# Esquematico.net
KiCad netlist of a schematic drawn in EAGLE
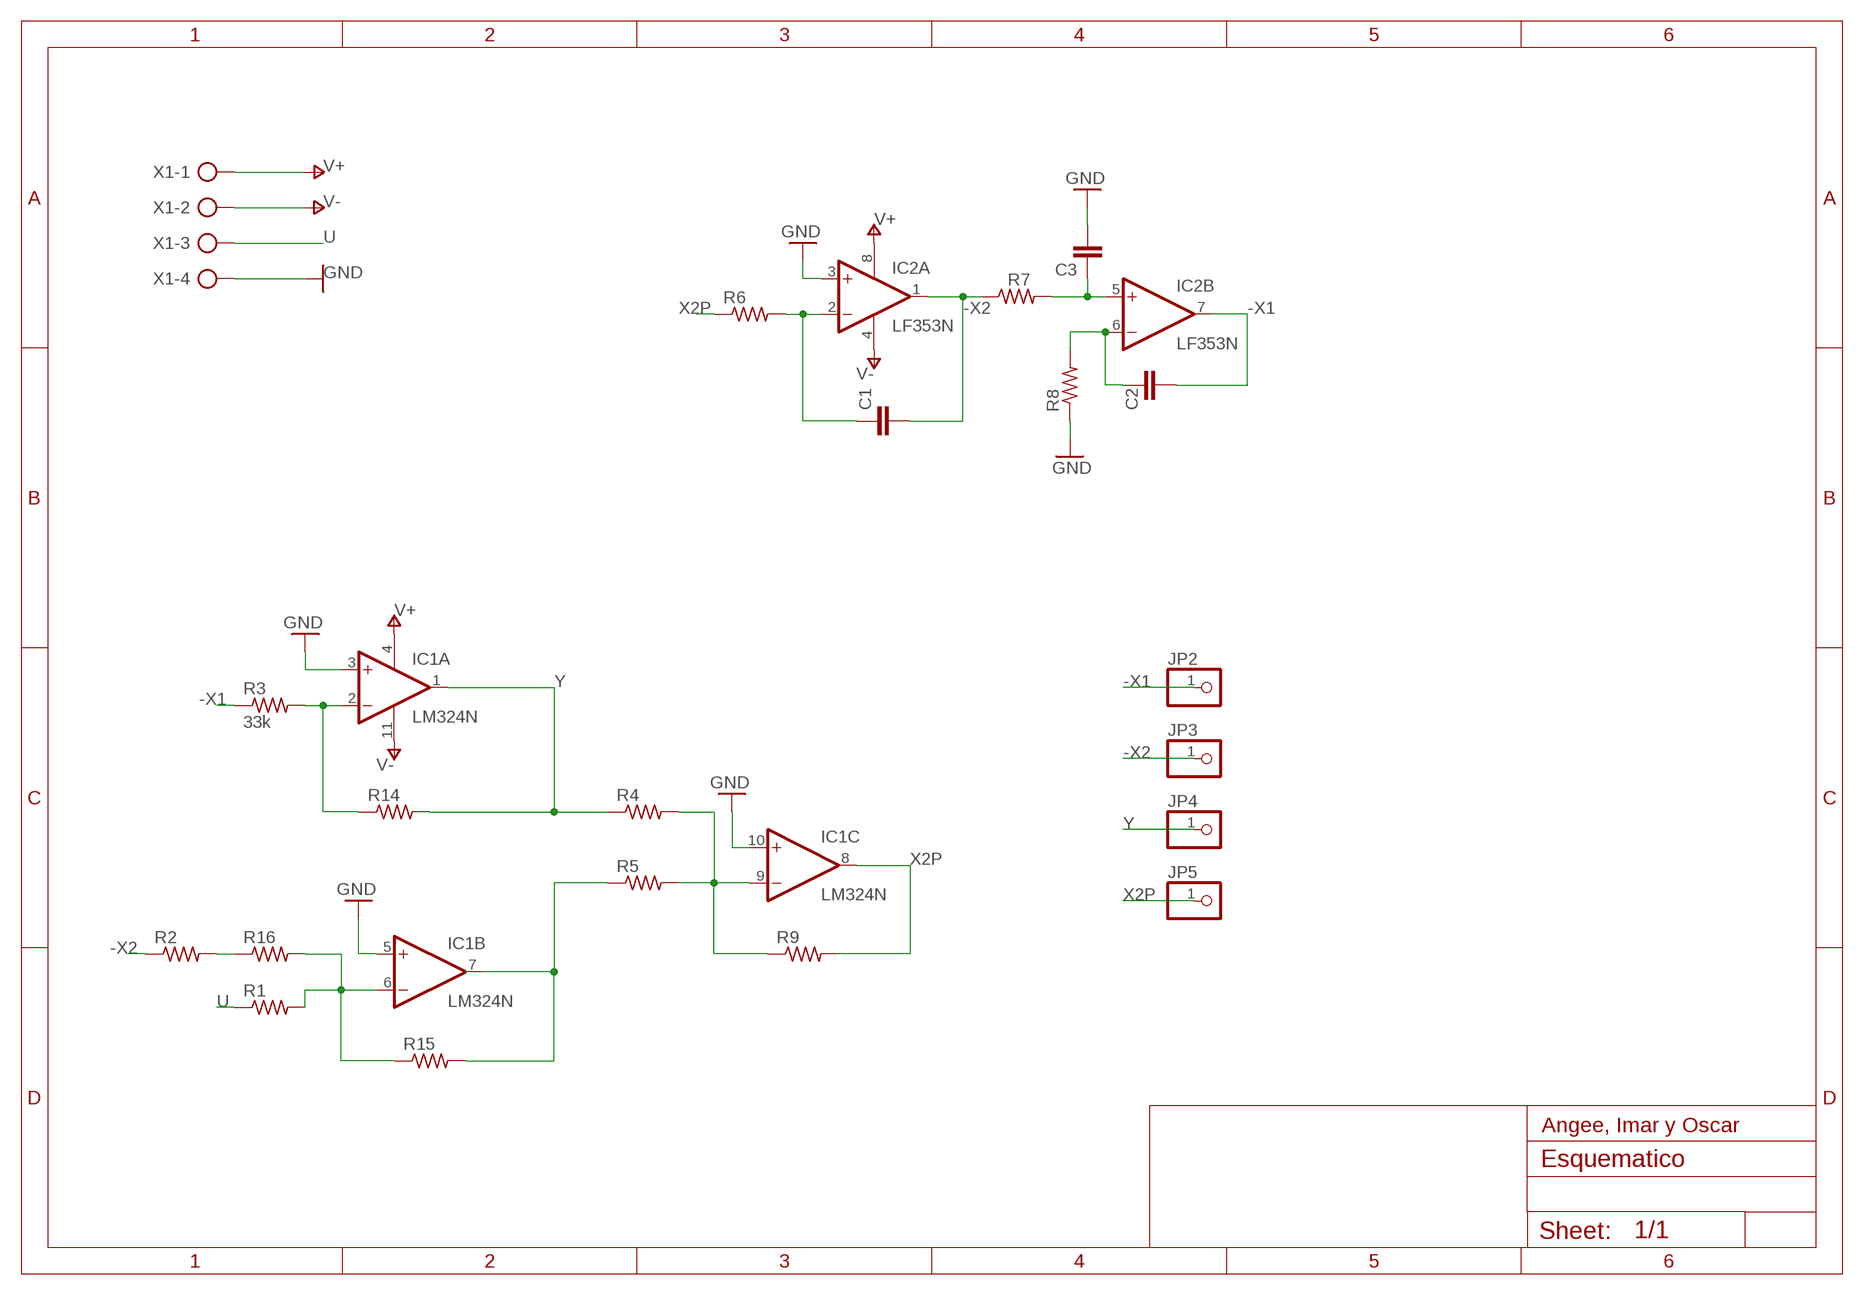
[diagram p0: schematic, sheet 1]

(export (version "E")
  (design (tool "Eeschema 10.0.6"))
  (components
    (comp (ref "C1")
      (value "C-EU150-054X183")
      (footprint "eagle-import:C150-054X183")
      (libsource (lib "eagle-import") (part "C-EU150-054X183"))
    )
    (comp (ref "C2")
      (value "C-EU150-054X183")
      (footprint "eagle-import:C150-054X183")
      (libsource (lib "eagle-import") (part "C-EU150-054X183"))
    )
    (comp (ref "C3")
      (value "C-EU150-054X183")
      (footprint "eagle-import:C150-054X183")
      (libsource (lib "eagle-import") (part "C-EU150-054X183"))
    )
    (comp (ref "IC1")
      (value "LM324N")
      (footprint "eagle-import:DIL14")
      (libsource (lib "eagle-import") (part "LM324N"))
    )
    (comp (ref "IC2")
      (value "LF353N")
      (footprint "eagle-import:DIL08")
      (libsource (lib "eagle-import") (part "LF353N"))
    )
    (comp (ref "JP2")
      (value "PINHD-1X1")
      (footprint "eagle-import:1X01")
      (libsource (lib "eagle-import") (part "PINHD-1X1"))
    )
    (comp (ref "JP3")
      (value "PINHD-1X1")
      (footprint "eagle-import:1X01")
      (libsource (lib "eagle-import") (part "PINHD-1X1"))
    )
    (comp (ref "JP4")
      (value "PINHD-1X1")
      (footprint "eagle-import:1X01")
      (libsource (lib "eagle-import") (part "PINHD-1X1"))
    )
    (comp (ref "JP5")
      (value "PINHD-1X1")
      (footprint "eagle-import:1X01")
      (libsource (lib "eagle-import") (part "PINHD-1X1"))
    )
    (comp (ref "R1")
      (value "R-US_0204/7")
      (footprint "eagle-import:0204_7")
      (libsource (lib "eagle-import") (part "R-US_0204/7"))
    )
    (comp (ref "R2")
      (value "R-US_0204/7")
      (footprint "eagle-import:0204_7")
      (libsource (lib "eagle-import") (part "R-US_0204/7"))
    )
    (comp (ref "R3")
      (value "33k")
      (footprint "eagle-import:0204_7")
      (libsource (lib "eagle-import") (part "R-US_0204/7"))
    )
    (comp (ref "R4")
      (value "R-US_0204/7")
      (footprint "eagle-import:0204_7")
      (libsource (lib "eagle-import") (part "R-US_0204/7"))
    )
    (comp (ref "R5")
      (value "R-US_0204/7")
      (footprint "eagle-import:0204_7")
      (libsource (lib "eagle-import") (part "R-US_0204/7"))
    )
    (comp (ref "R6")
      (value "R-US_0204/7")
      (footprint "eagle-import:0204_7")
      (libsource (lib "eagle-import") (part "R-US_0204/7"))
    )
    (comp (ref "R7")
      (value "R-US_0204/7")
      (footprint "eagle-import:0204_7")
      (libsource (lib "eagle-import") (part "R-US_0204/7"))
    )
    (comp (ref "R8")
      (value "R-US_0204/7")
      (footprint "eagle-import:0204_7")
      (libsource (lib "eagle-import") (part "R-US_0204/7"))
    )
    (comp (ref "R9")
      (value "R-US_0204/7")
      (footprint "eagle-import:0204_7")
      (libsource (lib "eagle-import") (part "R-US_0204/7"))
    )
    (comp (ref "R14")
      (value "R-US_0204/7")
      (footprint "eagle-import:0204_7")
      (libsource (lib "eagle-import") (part "R-US_0204/7"))
    )
    (comp (ref "R15")
      (value "R-US_0204/7")
      (footprint "eagle-import:0204_7")
      (libsource (lib "eagle-import") (part "R-US_0204/7"))
    )
    (comp (ref "R16")
      (value "R-US_0204/7")
      (footprint "eagle-import:0204_7")
      (libsource (lib "eagle-import") (part "R-US_0204/7"))
    )
    (comp (ref "X1")
      (value "AK300/4")
      (footprint "eagle-import:AK300_4")
      (libsource (lib "eagle-import") (part "AK300/4"))
    )
  )
  (nets
    (net (code "1") (name "/-X1") (class "Default")
      (node (ref "C2") (pin "2") (pinfunction "2_2") (pintype "passive"))
      (node (ref "IC2") (pin "7") (pinfunction "OUT_7") (pintype "output"))
      (node (ref "JP2") (pin "1") (pinfunction "1_1") (pintype "passive"))
      (node (ref "R3") (pin "1") (pinfunction "1_1") (pintype "passive"))
    )
    (net (code "2") (name "/-X2") (class "Default")
      (node (ref "C1") (pin "2") (pinfunction "2_2") (pintype "passive"))
      (node (ref "IC2") (pin "1") (pinfunction "OUT_1") (pintype "output"))
      (node (ref "JP3") (pin "1") (pinfunction "1_1") (pintype "passive"))
      (node (ref "R2") (pin "1") (pinfunction "1_1") (pintype "passive"))
      (node (ref "R7") (pin "1") (pinfunction "1_1") (pintype "passive"))
    )
    (net (code "3") (name "/U") (class "Default")
      (node (ref "R1") (pin "1") (pinfunction "1_1") (pintype "passive"))
      (node (ref "X1") (pin "3") (pinfunction "KL_3") (pintype "passive"))
    )
    (net (code "4") (name "/X2P") (class "Default")
      (node (ref "IC1") (pin "8") (pinfunction "OUT_8") (pintype "output"))
      (node (ref "JP5") (pin "1") (pinfunction "1_1") (pintype "passive"))
      (node (ref "R6") (pin "1") (pinfunction "1_1") (pintype "passive"))
      (node (ref "R9") (pin "2") (pinfunction "2_2") (pintype "passive"))
    )
    (net (code "5") (name "/Y") (class "Default")
      (node (ref "IC1") (pin "1") (pinfunction "OUT_1") (pintype "output"))
      (node (ref "JP4") (pin "1") (pinfunction "1_1") (pintype "passive"))
      (node (ref "R14") (pin "2") (pinfunction "2_2") (pintype "passive"))
      (node (ref "R4") (pin "1") (pinfunction "1_1") (pintype "passive"))
    )
    (net (code "6") (name "GND") (class "Default")
      (node (ref "C3") (pin "2") (pinfunction "2_2") (pintype "passive"))
      (node (ref "IC1") (pin "10") (pinfunction "+IN_10") (pintype "input"))
      (node (ref "IC1") (pin "3") (pinfunction "+IN_3") (pintype "input"))
      (node (ref "IC1") (pin "5") (pinfunction "+IN_5") (pintype "input"))
      (node (ref "IC2") (pin "3") (pinfunction "+IN_3") (pintype "input"))
      (node (ref "R8") (pin "1") (pinfunction "1_1") (pintype "passive"))
      (node (ref "X1") (pin "4") (pinfunction "KL_4") (pintype "passive"))
    )
    (net (code "7") (name "Net-(IC1A--IN)") (class "Default")
      (node (ref "IC1") (pin "2") (pinfunction "-IN_2") (pintype "input"))
      (node (ref "R14") (pin "1") (pinfunction "1_1") (pintype "passive"))
      (node (ref "R3") (pin "2") (pinfunction "2_2") (pintype "passive"))
    )
    (net (code "8") (name "Net-(IC1B--IN)") (class "Default")
      (node (ref "IC1") (pin "6") (pinfunction "-IN_6") (pintype "input"))
      (node (ref "R1") (pin "2") (pinfunction "2_2") (pintype "passive"))
      (node (ref "R15") (pin "1") (pinfunction "1_1") (pintype "passive"))
      (node (ref "R16") (pin "2") (pinfunction "2_2") (pintype "passive"))
    )
    (net (code "9") (name "Net-(IC1B-OUT)") (class "Default")
      (node (ref "IC1") (pin "7") (pinfunction "OUT_7") (pintype "output"))
      (node (ref "R15") (pin "2") (pinfunction "2_2") (pintype "passive"))
      (node (ref "R5") (pin "1") (pinfunction "1_1") (pintype "passive"))
    )
    (net (code "10") (name "Net-(IC1C--IN)") (class "Default")
      (node (ref "IC1") (pin "9") (pinfunction "-IN_9") (pintype "input"))
      (node (ref "R4") (pin "2") (pinfunction "2_2") (pintype "passive"))
      (node (ref "R5") (pin "2") (pinfunction "2_2") (pintype "passive"))
      (node (ref "R9") (pin "1") (pinfunction "1_1") (pintype "passive"))
    )
    (net (code "11") (name "Net-(IC2A--IN)") (class "Default")
      (node (ref "C1") (pin "1") (pinfunction "1_1") (pintype "passive"))
      (node (ref "IC2") (pin "2") (pinfunction "-IN_2") (pintype "input"))
      (node (ref "R6") (pin "2") (pinfunction "2_2") (pintype "passive"))
    )
    (net (code "12") (name "Net-(IC2B-+IN)") (class "Default")
      (node (ref "C3") (pin "1") (pinfunction "1_1") (pintype "passive"))
      (node (ref "IC2") (pin "5") (pinfunction "+IN_5") (pintype "input"))
      (node (ref "R7") (pin "2") (pinfunction "2_2") (pintype "passive"))
    )
    (net (code "13") (name "Net-(IC2B--IN)") (class "Default")
      (node (ref "C2") (pin "1") (pinfunction "1_1") (pintype "passive"))
      (node (ref "IC2") (pin "6") (pinfunction "-IN_6") (pintype "input"))
      (node (ref "R8") (pin "2") (pinfunction "2_2") (pintype "passive"))
    )
    (net (code "14") (name "Net-(R16-Pad1)") (class "Default")
      (node (ref "R16") (pin "1") (pinfunction "1_1") (pintype "passive"))
      (node (ref "R2") (pin "2") (pinfunction "2_2") (pintype "passive"))
    )
    (net (code "15") (name "V+") (class "Default")
      (node (ref "IC1") (pin "4") (pinfunction "V+_4") (pintype "power_in"))
      (node (ref "IC2") (pin "8") (pinfunction "V+_8") (pintype "power_in"))
      (node (ref "X1") (pin "1") (pinfunction "KL_1") (pintype "passive"))
    )
    (net (code "16") (name "V-") (class "Default")
      (node (ref "IC1") (pin "11") (pinfunction "V-_11") (pintype "power_in"))
      (node (ref "IC2") (pin "4") (pinfunction "V-_4") (pintype "power_in"))
      (node (ref "X1") (pin "2") (pinfunction "KL_2") (pintype "passive"))
    )
  )
)
